# RainwaterController.net
KiCad netlist of a schematic drawn in EAGLE
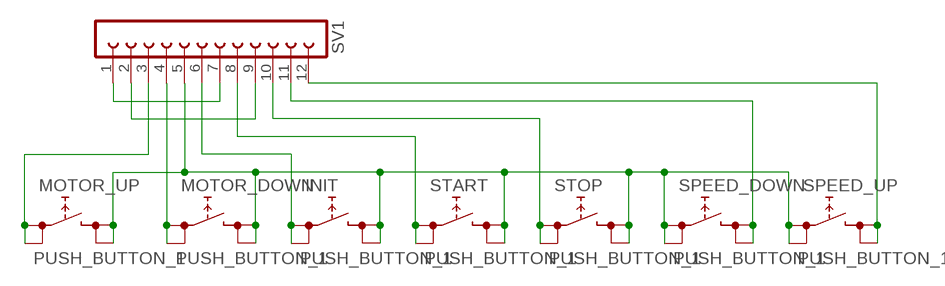
[diagram p0: schematic, sheet 1]

(export (version "E")
  (design (tool "Eeschema 10.0.6"))
  (components
    (comp (ref "INIT")
      (value "PUSH_BUTTON_1")
      (footprint "eagle-import:PUSHBUTTON")
      (libsource (lib "eagle-import") (part "PUSH_BUTTON_1"))
    )
    (comp (ref "MOTOR_DOWN")
      (value "PUSH_BUTTON_1")
      (footprint "eagle-import:PUSHBUTTON")
      (libsource (lib "eagle-import") (part "PUSH_BUTTON_1"))
    )
    (comp (ref "MOTOR_UP")
      (value "PUSH_BUTTON_1")
      (footprint "eagle-import:PUSHBUTTON")
      (libsource (lib "eagle-import") (part "PUSH_BUTTON_1"))
    )
    (comp (ref "SPEED_DOWN")
      (value "PUSH_BUTTON_1")
      (footprint "eagle-import:PUSHBUTTON")
      (libsource (lib "eagle-import") (part "PUSH_BUTTON_1"))
    )
    (comp (ref "SPEED_UP")
      (value "PUSH_BUTTON_1")
      (footprint "eagle-import:PUSHBUTTON")
      (libsource (lib "eagle-import") (part "PUSH_BUTTON_1"))
    )
    (comp (ref "START")
      (value "PUSH_BUTTON_1")
      (footprint "eagle-import:PUSHBUTTON")
      (libsource (lib "eagle-import") (part "PUSH_BUTTON_1"))
    )
    (comp (ref "STOP")
      (value "PUSH_BUTTON_1")
      (footprint "eagle-import:PUSHBUTTON")
      (libsource (lib "eagle-import") (part "PUSH_BUTTON_1"))
    )
    (comp (ref "SV1")
      (value "FE12-1")
      (footprint "eagle-import:FE12")
      (libsource (lib "eagle-import") (part "FE12-1"))
    )
  )
  (nets
    (net (code "1") (name "Net-(INIT-P1)") (class "Default")
      (node (ref "INIT") (pin "P$1") (pinfunction "P1_P$1") (pintype "passive"))
      (node (ref "INIT") (pin "P$2") (pinfunction "P2_P$2") (pintype "passive"))
      (node (ref "SV1") (pin "6") (pinfunction "6_6") (pintype "passive"))
    )
    (net (code "2") (name "Net-(INIT-P3)") (class "Default")
      (node (ref "INIT") (pin "P$3") (pinfunction "P3_P$3") (pintype "passive"))
      (node (ref "INIT") (pin "P$4") (pinfunction "P4_P$4") (pintype "passive"))
      (node (ref "MOTOR_DOWN") (pin "P$3") (pinfunction "P3_P$3") (pintype "passive"))
      (node (ref "MOTOR_DOWN") (pin "P$4") (pinfunction "P4_P$4") (pintype "passive"))
      (node (ref "MOTOR_UP") (pin "P$3") (pinfunction "P3_P$3") (pintype "passive"))
      (node (ref "MOTOR_UP") (pin "P$4") (pinfunction "P4_P$4") (pintype "passive"))
      (node (ref "SPEED_DOWN") (pin "P$1") (pinfunction "P1_P$1") (pintype "passive"))
      (node (ref "SPEED_DOWN") (pin "P$2") (pinfunction "P2_P$2") (pintype "passive"))
      (node (ref "SPEED_UP") (pin "P$1") (pinfunction "P1_P$1") (pintype "passive"))
      (node (ref "SPEED_UP") (pin "P$2") (pinfunction "P2_P$2") (pintype "passive"))
      (node (ref "START") (pin "P$3") (pinfunction "P3_P$3") (pintype "passive"))
      (node (ref "START") (pin "P$4") (pinfunction "P4_P$4") (pintype "passive"))
      (node (ref "STOP") (pin "P$3") (pinfunction "P3_P$3") (pintype "passive"))
      (node (ref "STOP") (pin "P$4") (pinfunction "P4_P$4") (pintype "passive"))
      (node (ref "SV1") (pin "5") (pinfunction "5_5") (pintype "passive"))
    )
    (net (code "3") (name "Net-(MOTOR_DOWN-P1)") (class "Default")
      (node (ref "MOTOR_DOWN") (pin "P$1") (pinfunction "P1_P$1") (pintype "passive"))
      (node (ref "MOTOR_DOWN") (pin "P$2") (pinfunction "P2_P$2") (pintype "passive"))
      (node (ref "SV1") (pin "4") (pinfunction "4_4") (pintype "passive"))
    )
    (net (code "4") (name "Net-(MOTOR_UP-P1)") (class "Default")
      (node (ref "MOTOR_UP") (pin "P$1") (pinfunction "P1_P$1") (pintype "passive"))
      (node (ref "MOTOR_UP") (pin "P$2") (pinfunction "P2_P$2") (pintype "passive"))
      (node (ref "SV1") (pin "3") (pinfunction "3_3") (pintype "passive"))
    )
    (net (code "5") (name "Net-(SPEED_DOWN-P3)") (class "Default")
      (node (ref "SPEED_DOWN") (pin "P$3") (pinfunction "P3_P$3") (pintype "passive"))
      (node (ref "SPEED_DOWN") (pin "P$4") (pinfunction "P4_P$4") (pintype "passive"))
      (node (ref "SV1") (pin "11") (pinfunction "11_11") (pintype "passive"))
    )
    (net (code "6") (name "Net-(SPEED_UP-P3)") (class "Default")
      (node (ref "SPEED_UP") (pin "P$3") (pinfunction "P3_P$3") (pintype "passive"))
      (node (ref "SPEED_UP") (pin "P$4") (pinfunction "P4_P$4") (pintype "passive"))
      (node (ref "SV1") (pin "12") (pinfunction "12_12") (pintype "passive"))
    )
    (net (code "7") (name "Net-(START-P1)") (class "Default")
      (node (ref "START") (pin "P$1") (pinfunction "P1_P$1") (pintype "passive"))
      (node (ref "START") (pin "P$2") (pinfunction "P2_P$2") (pintype "passive"))
      (node (ref "SV1") (pin "8") (pinfunction "8_8") (pintype "passive"))
    )
    (net (code "8") (name "Net-(STOP-P1)") (class "Default")
      (node (ref "STOP") (pin "P$1") (pinfunction "P1_P$1") (pintype "passive"))
      (node (ref "STOP") (pin "P$2") (pinfunction "P2_P$2") (pintype "passive"))
      (node (ref "SV1") (pin "10") (pinfunction "10_10") (pintype "passive"))
    )
    (net (code "9") (name "Net-(SV1-Pad1)") (class "Default")
      (node (ref "SV1") (pin "1") (pinfunction "1_1") (pintype "passive"))
      (node (ref "SV1") (pin "7") (pinfunction "7_7") (pintype "passive"))
    )
    (net (code "10") (name "Net-(SV1-Pad2)") (class "Default")
      (node (ref "SV1") (pin "2") (pinfunction "2_2") (pintype "passive"))
      (node (ref "SV1") (pin "9") (pinfunction "9_9") (pintype "passive"))
    )
  )
)
